# untitled.net
KiCad netlist of a schematic drawn in EAGLE
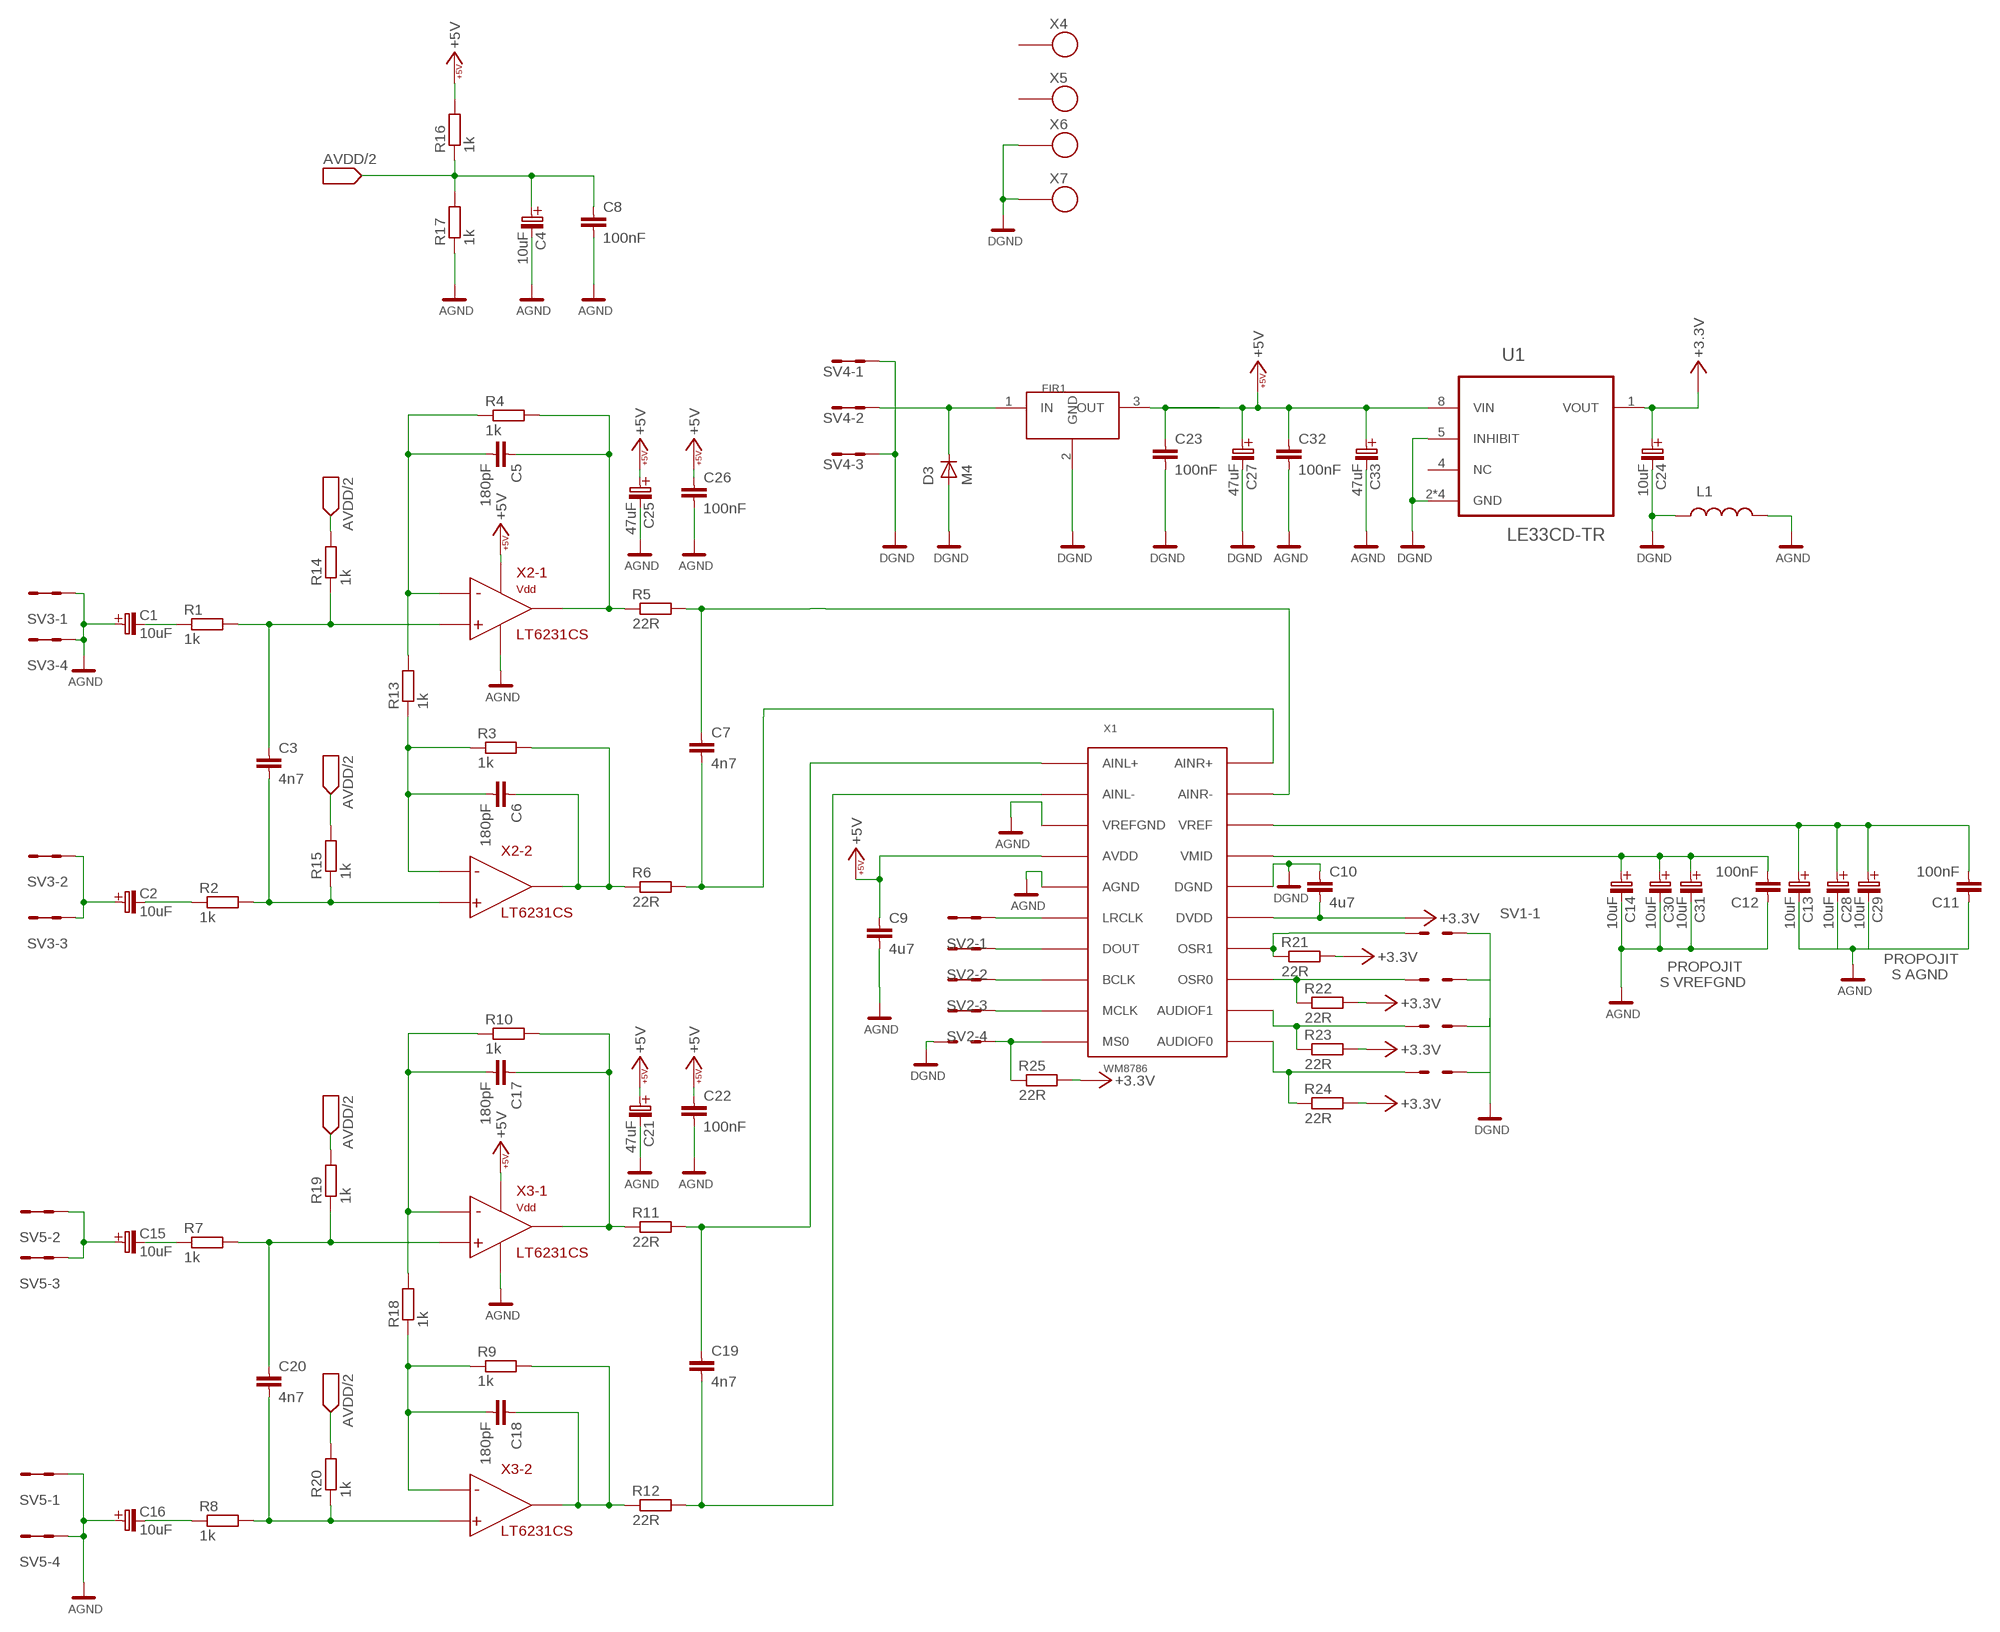
[diagram p0: schematic, sheet 1]

(export (version "E")
  (design (tool "Eeschema 10.0.6"))
  (components
    (comp (ref "C1") (value "10uF") (footprint "eagle-import:B") (libsource (lib "eagle-import") (part "B")))
    (comp (ref "C2") (value "10uF") (footprint "eagle-import:B") (libsource (lib "eagle-import") (part "B")))
    (comp (ref "C3")
      (value "4n7")
      (footprint "eagle-import:C0805")
      (libsource (lib "eagle-import") (part "C0805"))
    )
    (comp (ref "C4") (value "10uF") (footprint "eagle-import:B") (libsource (lib "eagle-import") (part "B")))
    (comp (ref "C5")
      (value "180pF")
      (footprint "eagle-import:C0805")
      (libsource (lib "eagle-import") (part "C0805"))
    )
    (comp (ref "C6")
      (value "180pF")
      (footprint "eagle-import:C0805")
      (libsource (lib "eagle-import") (part "C0805"))
    )
    (comp (ref "C7")
      (value "4n7")
      (footprint "eagle-import:C0805")
      (libsource (lib "eagle-import") (part "C0805"))
    )
    (comp (ref "C8")
      (value "100nF")
      (footprint "eagle-import:C0805")
      (libsource (lib "eagle-import") (part "C0805"))
    )
    (comp (ref "C9")
      (value "4u7")
      (footprint "eagle-import:C0805")
      (libsource (lib "eagle-import") (part "C0805"))
    )
    (comp (ref "C10")
      (value "4u7")
      (footprint "eagle-import:C0805")
      (libsource (lib "eagle-import") (part "C0805"))
    )
    (comp (ref "C11")
      (value "100nF")
      (footprint "eagle-import:C0805")
      (libsource (lib "eagle-import") (part "C0805"))
    )
    (comp (ref "C12")
      (value "100nF")
      (footprint "eagle-import:C0805")
      (libsource (lib "eagle-import") (part "C0805"))
    )
    (comp (ref "C13") (value "10uF") (footprint "eagle-import:B") (libsource (lib "eagle-import") (part "B")))
    (comp (ref "C14") (value "10uF") (footprint "eagle-import:B") (libsource (lib "eagle-import") (part "B")))
    (comp (ref "C15") (value "10uF") (footprint "eagle-import:B") (libsource (lib "eagle-import") (part "B")))
    (comp (ref "C16") (value "10uF") (footprint "eagle-import:B") (libsource (lib "eagle-import") (part "B")))
    (comp (ref "C17")
      (value "180pF")
      (footprint "eagle-import:C0805")
      (libsource (lib "eagle-import") (part "C0805"))
    )
    (comp (ref "C18")
      (value "180pF")
      (footprint "eagle-import:C0805")
      (libsource (lib "eagle-import") (part "C0805"))
    )
    (comp (ref "C19")
      (value "4n7")
      (footprint "eagle-import:C0805")
      (libsource (lib "eagle-import") (part "C0805"))
    )
    (comp (ref "C20")
      (value "4n7")
      (footprint "eagle-import:C0805")
      (libsource (lib "eagle-import") (part "C0805"))
    )
    (comp (ref "C21") (value "47uF") (footprint "eagle-import:B") (libsource (lib "eagle-import") (part "B")))
    (comp (ref "C22")
      (value "100nF")
      (footprint "eagle-import:C0805")
      (libsource (lib "eagle-import") (part "C0805"))
    )
    (comp (ref "C23")
      (value "100nF")
      (footprint "eagle-import:C0805")
      (libsource (lib "eagle-import") (part "C0805"))
    )
    (comp (ref "C24") (value "10uF") (footprint "eagle-import:B") (libsource (lib "eagle-import") (part "B")))
    (comp (ref "C25") (value "47uF") (footprint "eagle-import:B") (libsource (lib "eagle-import") (part "B")))
    (comp (ref "C26")
      (value "100nF")
      (footprint "eagle-import:C0805")
      (libsource (lib "eagle-import") (part "C0805"))
    )
    (comp (ref "C27") (value "47uF") (footprint "eagle-import:B") (libsource (lib "eagle-import") (part "B")))
    (comp (ref "C28") (value "10uF") (footprint "eagle-import:B") (libsource (lib "eagle-import") (part "B")))
    (comp (ref "C29") (value "10uF") (footprint "eagle-import:B") (libsource (lib "eagle-import") (part "B")))
    (comp (ref "C30") (value "10uF") (footprint "eagle-import:B") (libsource (lib "eagle-import") (part "B")))
    (comp (ref "C31") (value "10uF") (footprint "eagle-import:B") (libsource (lib "eagle-import") (part "B")))
    (comp (ref "C32")
      (value "100nF")
      (footprint "eagle-import:C0805")
      (libsource (lib "eagle-import") (part "C0805"))
    )
    (comp (ref "C33") (value "47uF") (footprint "eagle-import:B") (libsource (lib "eagle-import") (part "B")))
    (comp (ref "D3")
      (value "M4")
      (footprint "eagle-import:SMA")
      (libsource (lib "eagle-import") (part "D-OB.SMA"))
    )
    (comp (ref "FIR1")
      (value "FILTR0805")
      (footprint "eagle-import:F0805")
      (libsource (lib "eagle-import") (part "FILTR0805"))
    )
    (comp (ref "L1")
      (value "L0805")
      (footprint "eagle-import:L0805")
      (libsource (lib "eagle-import") (part "L0805"))
    )
    (comp (ref "R1")
      (value "1k")
      (footprint "eagle-import:0805")
      (libsource (lib "eagle-import") (part "R0805"))
    )
    (comp (ref "R2")
      (value "1k")
      (footprint "eagle-import:0805")
      (libsource (lib "eagle-import") (part "R0805"))
    )
    (comp (ref "R3")
      (value "1k")
      (footprint "eagle-import:0805")
      (libsource (lib "eagle-import") (part "R0805"))
    )
    (comp (ref "R4")
      (value "1k")
      (footprint "eagle-import:0805")
      (libsource (lib "eagle-import") (part "R0805"))
    )
    (comp (ref "R5")
      (value "22R")
      (footprint "eagle-import:0805")
      (libsource (lib "eagle-import") (part "R0805"))
    )
    (comp (ref "R6")
      (value "22R")
      (footprint "eagle-import:0805")
      (libsource (lib "eagle-import") (part "R0805"))
    )
    (comp (ref "R7")
      (value "1k")
      (footprint "eagle-import:0805")
      (libsource (lib "eagle-import") (part "R0805"))
    )
    (comp (ref "R8")
      (value "1k")
      (footprint "eagle-import:0805")
      (libsource (lib "eagle-import") (part "R0805"))
    )
    (comp (ref "R9")
      (value "1k")
      (footprint "eagle-import:0805")
      (libsource (lib "eagle-import") (part "R0805"))
    )
    (comp (ref "R10")
      (value "1k")
      (footprint "eagle-import:0805")
      (libsource (lib "eagle-import") (part "R0805"))
    )
    (comp (ref "R11")
      (value "22R")
      (footprint "eagle-import:0805")
      (libsource (lib "eagle-import") (part "R0805"))
    )
    (comp (ref "R12")
      (value "22R")
      (footprint "eagle-import:0805")
      (libsource (lib "eagle-import") (part "R0805"))
    )
    (comp (ref "R13")
      (value "1k")
      (footprint "eagle-import:0805")
      (libsource (lib "eagle-import") (part "R0805"))
    )
    (comp (ref "R14")
      (value "1k")
      (footprint "eagle-import:0805")
      (libsource (lib "eagle-import") (part "R0805"))
    )
    (comp (ref "R15")
      (value "1k")
      (footprint "eagle-import:0805")
      (libsource (lib "eagle-import") (part "R0805"))
    )
    (comp (ref "R16")
      (value "1k")
      (footprint "eagle-import:0805")
      (libsource (lib "eagle-import") (part "R0805"))
    )
    (comp (ref "R17")
      (value "1k")
      (footprint "eagle-import:0805")
      (libsource (lib "eagle-import") (part "R0805"))
    )
    (comp (ref "R18")
      (value "1k")
      (footprint "eagle-import:0805")
      (libsource (lib "eagle-import") (part "R0805"))
    )
    (comp (ref "R19")
      (value "1k")
      (footprint "eagle-import:0805")
      (libsource (lib "eagle-import") (part "R0805"))
    )
    (comp (ref "R20")
      (value "1k")
      (footprint "eagle-import:0805")
      (libsource (lib "eagle-import") (part "R0805"))
    )
    (comp (ref "R21")
      (value "22R")
      (footprint "eagle-import:0805")
      (libsource (lib "eagle-import") (part "R0805"))
    )
    (comp (ref "R22")
      (value "22R")
      (footprint "eagle-import:0805")
      (libsource (lib "eagle-import") (part "R0805"))
    )
    (comp (ref "R23")
      (value "22R")
      (footprint "eagle-import:0805")
      (libsource (lib "eagle-import") (part "R0805"))
    )
    (comp (ref "R24")
      (value "22R")
      (footprint "eagle-import:0805")
      (libsource (lib "eagle-import") (part "R0805"))
    )
    (comp (ref "R25")
      (value "22R")
      (footprint "eagle-import:0805")
      (libsource (lib "eagle-import") (part "R0805"))
    )
    (comp (ref "SV1")
      (value "MA05-3")
      (footprint "eagle-import:MA05-2")
      (libsource (lib "eagle-import") (part "MA05-3"))
    )
    (comp (ref "SV2")
      (value "MA04-2")
      (footprint "eagle-import:MA04-2")
      (libsource (lib "eagle-import") (part "MA04-2"))
    )
    (comp (ref "SV3")
      (value "MA04-2")
      (footprint "eagle-import:MA04-2")
      (libsource (lib "eagle-import") (part "MA04-2"))
    )
    (comp (ref "SV4")
      (value "MA03-2")
      (footprint "eagle-import:MA03-2")
      (libsource (lib "eagle-import") (part "MA03-2"))
    )
    (comp (ref "SV5")
      (value "MA04-2")
      (footprint "eagle-import:MA04-2")
      (libsource (lib "eagle-import") (part "MA04-2"))
    )
    (comp (ref "U1")
      (value "LE33CD-TR")
      (footprint "eagle-import:SOIC127P600X175-8N")
      (libsource (lib "eagle-import") (part "LE33CD-TR"))
    )
    (comp (ref "X1")
      (value "WM8786")
      (footprint "eagle-import:SSOP20")
      (libsource (lib "eagle-import") (part "WM8786"))
    )
    (comp (ref "X2")
      (value "LT6231CS")
      (footprint "eagle-import:SO8")
      (libsource (lib "eagle-import") (part "LT6231CS"))
    )
    (comp (ref "X3")
      (value "LT6231CS")
      (footprint "eagle-import:SO8")
      (libsource (lib "eagle-import") (part "LT6231CS"))
    )
    (comp (ref "X4")
      (value "SROUB3M")
      (footprint "eagle-import:SROUB3M")
      (libsource (lib "eagle-import") (part "SROUB3M"))
    )
    (comp (ref "X5")
      (value "SROUB3M")
      (footprint "eagle-import:SROUB3M")
      (libsource (lib "eagle-import") (part "SROUB3M"))
    )
    (comp (ref "X6")
      (value "SROUB3M")
      (footprint "eagle-import:SROUB3M")
      (libsource (lib "eagle-import") (part "SROUB3M"))
    )
    (comp (ref "X7")
      (value "SROUB3M")
      (footprint "eagle-import:SROUB3M")
      (libsource (lib "eagle-import") (part "SROUB3M"))
    )
  )
  (nets
    (net (code "1") (name "+3.3V") (class "Default")
      (node (ref "C10") (pin "2") (pinfunction "2_2") (pintype "passive"))
      (node (ref "C24") (pin "+") (pinfunction "C_EL+_+") (pintype "passive"))
      (node (ref "R21") (pin "2") (pinfunction "2_2") (pintype "passive"))
      (node (ref "R22") (pin "2") (pinfunction "2_2") (pintype "passive"))
      (node (ref "R23") (pin "2") (pinfunction "2_2") (pintype "passive"))
      (node (ref "R24") (pin "2") (pinfunction "2_2") (pintype "passive"))
      (node (ref "R25") (pin "2") (pinfunction "2_2") (pintype "passive"))
      (node (ref "U1") (pin "1") (pinfunction "VOUT_1") (pintype "output"))
      (node (ref "X1") (pin "15") (pinfunction "DVDD_15") (pintype "bidirectional"))
    )
    (net (code "2") (name "+5V") (class "Default")
      (node (ref "C21") (pin "+") (pinfunction "C_EL+_+") (pintype "passive"))
      (node (ref "C22") (pin "1") (pinfunction "1_1") (pintype "passive"))
      (node (ref "C23") (pin "1") (pinfunction "1_1") (pintype "passive"))
      (node (ref "C25") (pin "+") (pinfunction "C_EL+_+") (pintype "passive"))
      (node (ref "C26") (pin "1") (pinfunction "1_1") (pintype "passive"))
      (node (ref "C27") (pin "+") (pinfunction "C_EL+_+") (pintype "passive"))
      (node (ref "C32") (pin "1") (pinfunction "1_1") (pintype "passive"))
      (node (ref "C33") (pin "+") (pinfunction "C_EL+_+") (pintype "passive"))
      (node (ref "C9") (pin "1") (pinfunction "1_1") (pintype "passive"))
      (node (ref "FIR1") (pin "3") (pinfunction "OUT_3") (pintype "bidirectional"))
      (node (ref "R16") (pin "2") (pinfunction "2_2") (pintype "passive"))
      (node (ref "U1") (pin "8") (pinfunction "VIN_8") (pintype "power_in"))
      (node (ref "X1") (pin "4") (pinfunction "AVDD_4") (pintype "bidirectional"))
      (node (ref "X2") (pin "8") (pinfunction "VDD_8") (pintype "bidirectional"))
      (node (ref "X3") (pin "8") (pinfunction "VDD_8") (pintype "bidirectional"))
    )
    (net (code "3") (name "/AVDD{slash}2") (class "Default")
      (node (ref "C4") (pin "+") (pinfunction "C_EL+_+") (pintype "passive"))
      (node (ref "C8") (pin "1") (pinfunction "1_1") (pintype "passive"))
      (node (ref "R14") (pin "2") (pinfunction "2_2") (pintype "passive"))
      (node (ref "R15") (pin "2") (pinfunction "2_2") (pintype "passive"))
      (node (ref "R16") (pin "1") (pinfunction "1_1") (pintype "passive"))
      (node (ref "R17") (pin "2") (pinfunction "2_2") (pintype "passive"))
      (node (ref "R19") (pin "2") (pinfunction "2_2") (pintype "passive"))
      (node (ref "R20") (pin "2") (pinfunction "2_2") (pintype "passive"))
    )
    (net (code "4") (name "AGND") (class "Default")
      (node (ref "C1") (pin "+") (pinfunction "C_EL+_+") (pintype "passive"))
      (node (ref "C11") (pin "1") (pinfunction "1_1") (pintype "passive"))
      (node (ref "C12") (pin "1") (pinfunction "1_1") (pintype "passive"))
      (node (ref "C13") (pin "-") (pinfunction "C_EL-_-") (pintype "passive"))
      (node (ref "C14") (pin "-") (pinfunction "C_EL-_-") (pintype "passive"))
      (node (ref "C16") (pin "+") (pinfunction "C_EL+_+") (pintype "passive"))
      (node (ref "C21") (pin "-") (pinfunction "C_EL-_-") (pintype "passive"))
      (node (ref "C22") (pin "2") (pinfunction "2_2") (pintype "passive"))
      (node (ref "C25") (pin "-") (pinfunction "C_EL-_-") (pintype "passive"))
      (node (ref "C26") (pin "2") (pinfunction "2_2") (pintype "passive"))
      (node (ref "C28") (pin "-") (pinfunction "C_EL-_-") (pintype "passive"))
      (node (ref "C29") (pin "-") (pinfunction "C_EL-_-") (pintype "passive"))
      (node (ref "C30") (pin "-") (pinfunction "C_EL-_-") (pintype "passive"))
      (node (ref "C31") (pin "-") (pinfunction "C_EL-_-") (pintype "passive"))
      (node (ref "C32") (pin "2") (pinfunction "2_2") (pintype "passive"))
      (node (ref "C33") (pin "-") (pinfunction "C_EL-_-") (pintype "passive"))
      (node (ref "C4") (pin "-") (pinfunction "C_EL-_-") (pintype "passive"))
      (node (ref "C8") (pin "2") (pinfunction "2_2") (pintype "passive"))
      (node (ref "C9") (pin "2") (pinfunction "2_2") (pintype "passive"))
      (node (ref "L1") (pin "2") (pinfunction "2_2") (pintype "passive"))
      (node (ref "R17") (pin "1") (pinfunction "1_1") (pintype "passive"))
      (node (ref "SV3") (pin "1") (pinfunction "K_1") (pintype "passive"))
      (node (ref "SV3") (pin "2") (pinfunction "K_2") (pintype "passive"))
      (node (ref "SV3") (pin "7") (pinfunction "K_7") (pintype "passive"))
      (node (ref "SV3") (pin "8") (pinfunction "K_8") (pintype "passive"))
      (node (ref "SV5") (pin "1") (pinfunction "K_1") (pintype "passive"))
      (node (ref "SV5") (pin "2") (pinfunction "K_2") (pintype "passive"))
      (node (ref "SV5") (pin "7") (pinfunction "K_7") (pintype "passive"))
      (node (ref "SV5") (pin "8") (pinfunction "K_8") (pintype "passive"))
      (node (ref "X1") (pin "3") (pinfunction "VREFGND_3") (pintype "bidirectional"))
      (node (ref "X1") (pin "5") (pinfunction "AGND_5") (pintype "bidirectional"))
      (node (ref "X2") (pin "4") (pinfunction "GND_4") (pintype "bidirectional"))
      (node (ref "X3") (pin "4") (pinfunction "GND_4") (pintype "bidirectional"))
    )
    (net (code "5") (name "DGND") (class "Default")
      (node (ref "C10") (pin "1") (pinfunction "1_1") (pintype "passive"))
      (node (ref "C23") (pin "2") (pinfunction "2_2") (pintype "passive"))
      (node (ref "C24") (pin "-") (pinfunction "C_EL-_-") (pintype "passive"))
      (node (ref "C27") (pin "-") (pinfunction "C_EL-_-") (pintype "passive"))
      (node (ref "D3") (pin "A") (pinfunction "A_A") (pintype "passive"))
      (node (ref "FIR1") (pin "2") (pinfunction "GND_2") (pintype "passive"))
      (node (ref "L1") (pin "1") (pinfunction "1_1") (pintype "passive"))
      (node (ref "SV1") (pin "1") (pinfunction "P$1_1") (pintype "passive"))
      (node (ref "SV1") (pin "3") (pinfunction "P$1_3") (pintype "passive"))
      (node (ref "SV1") (pin "5") (pinfunction "P$1_5") (pintype "passive"))
      (node (ref "SV1") (pin "7") (pinfunction "P$1_7") (pintype "passive"))
      (node (ref "SV1") (pin "9") (pinfunction "P$1_9") (pintype "passive"))
      (node (ref "SV4") (pin "1") (pinfunction "K_1") (pintype "passive"))
      (node (ref "SV4") (pin "2") (pinfunction "K_2") (pintype "passive"))
      (node (ref "SV4") (pin "5") (pinfunction "K_5") (pintype "passive"))
      (node (ref "SV4") (pin "6") (pinfunction "K_6") (pintype "passive"))
      (node (ref "U1") (pin "2") (pinfunction "GND_2") (pintype "passive"))
      (node (ref "U1") (pin "3") (pinfunction "GND_3") (pintype "passive"))
      (node (ref "U1") (pin "5") (pinfunction "INHIBIT_5") (pintype "passive"))
      (node (ref "U1") (pin "6") (pinfunction "GND_6") (pintype "passive"))
      (node (ref "U1") (pin "7") (pinfunction "GND_7") (pintype "passive"))
      (node (ref "X1") (pin "16") (pinfunction "DGND_16") (pintype "bidirectional"))
      (node (ref "X6") (pin "P$1") (pinfunction "P$1_P$1") (pintype "bidirectional"))
      (node (ref "X7") (pin "P$1") (pinfunction "P$1_P$1") (pintype "bidirectional"))
    )
    (net (code "6") (name "Net-(C1-C_EL-)") (class "Default")
      (node (ref "C1") (pin "-") (pinfunction "C_EL-_-") (pintype "passive"))
      (node (ref "R1") (pin "1") (pinfunction "1_1") (pintype "passive"))
    )
    (net (code "7") (name "Net-(C2-C_EL+)") (class "Default")
      (node (ref "C2") (pin "+") (pinfunction "C_EL+_+") (pintype "passive"))
      (node (ref "SV3") (pin "3") (pinfunction "K_3") (pintype "passive"))
      (node (ref "SV3") (pin "4") (pinfunction "K_4") (pintype "passive"))
      (node (ref "SV3") (pin "5") (pinfunction "K_5") (pintype "passive"))
      (node (ref "SV3") (pin "6") (pinfunction "K_6") (pintype "passive"))
    )
    (net (code "8") (name "Net-(C2-C_EL-)") (class "Default")
      (node (ref "C2") (pin "-") (pinfunction "C_EL-_-") (pintype "passive"))
      (node (ref "R2") (pin "1") (pinfunction "1_1") (pintype "passive"))
    )
    (net (code "9") (name "Net-(C13-C_EL+)") (class "Default")
      (node (ref "C11") (pin "2") (pinfunction "2_2") (pintype "passive"))
      (node (ref "C13") (pin "+") (pinfunction "C_EL+_+") (pintype "passive"))
      (node (ref "C28") (pin "+") (pinfunction "C_EL+_+") (pintype "passive"))
      (node (ref "C29") (pin "+") (pinfunction "C_EL+_+") (pintype "passive"))
      (node (ref "X1") (pin "18") (pinfunction "VREF_18") (pintype "bidirectional"))
    )
    (net (code "10") (name "Net-(C14-C_EL+)") (class "Default")
      (node (ref "C12") (pin "2") (pinfunction "2_2") (pintype "passive"))
      (node (ref "C14") (pin "+") (pinfunction "C_EL+_+") (pintype "passive"))
      (node (ref "C30") (pin "+") (pinfunction "C_EL+_+") (pintype "passive"))
      (node (ref "C31") (pin "+") (pinfunction "C_EL+_+") (pintype "passive"))
      (node (ref "X1") (pin "17") (pinfunction "VMID_17") (pintype "bidirectional"))
    )
    (net (code "11") (name "Net-(C15-C_EL+)") (class "Default")
      (node (ref "C15") (pin "+") (pinfunction "C_EL+_+") (pintype "passive"))
      (node (ref "SV5") (pin "3") (pinfunction "K_3") (pintype "passive"))
      (node (ref "SV5") (pin "4") (pinfunction "K_4") (pintype "passive"))
      (node (ref "SV5") (pin "5") (pinfunction "K_5") (pintype "passive"))
      (node (ref "SV5") (pin "6") (pinfunction "K_6") (pintype "passive"))
    )
    (net (code "12") (name "Net-(C15-C_EL-)") (class "Default")
      (node (ref "C15") (pin "-") (pinfunction "C_EL-_-") (pintype "passive"))
      (node (ref "R7") (pin "1") (pinfunction "1_1") (pintype "passive"))
    )
    (net (code "13") (name "Net-(C16-C_EL-)") (class "Default")
      (node (ref "C16") (pin "-") (pinfunction "C_EL-_-") (pintype "passive"))
      (node (ref "R8") (pin "1") (pinfunction "1_1") (pintype "passive"))
    )
    (net (code "14") (name "Net-(D3-C)") (class "Default")
      (node (ref "D3") (pin "K") (pinfunction "C_K") (pintype "passive"))
      (node (ref "FIR1") (pin "1") (pinfunction "IN_1") (pintype "bidirectional"))
      (node (ref "SV4") (pin "3") (pinfunction "K_3") (pintype "passive"))
      (node (ref "SV4") (pin "4") (pinfunction "K_4") (pintype "passive"))
    )
    (net (code "15") (name "Net-(SV1B-P$1)") (class "Default")
      (node (ref "R25") (pin "1") (pinfunction "1_1") (pintype "passive"))
      (node (ref "SV1") (pin "10") (pinfunction "P$1_10") (pintype "passive"))
      (node (ref "X1") (pin "10") (pinfunction "MS0_10") (pintype "bidirectional"))
    )
    (net (code "16") (name "Net-(SV1C-P$1)") (class "Default")
      (node (ref "R21") (pin "1") (pinfunction "1_1") (pintype "passive"))
      (node (ref "SV1") (pin "2") (pinfunction "P$1_2") (pintype "passive"))
      (node (ref "X1") (pin "14") (pinfunction "OSR1_14") (pintype "bidirectional"))
    )
    (net (code "17") (name "Net-(SV1E-P$1)") (class "Default")
      (node (ref "R22") (pin "1") (pinfunction "1_1") (pintype "passive"))
      (node (ref "SV1") (pin "4") (pinfunction "P$1_4") (pintype "passive"))
      (node (ref "X1") (pin "13") (pinfunction "OSR0_13") (pintype "bidirectional"))
    )
    (net (code "18") (name "Net-(SV1G-P$1)") (class "Default")
      (node (ref "R23") (pin "1") (pinfunction "1_1") (pintype "passive"))
      (node (ref "SV1") (pin "6") (pinfunction "P$1_6") (pintype "passive"))
      (node (ref "X1") (pin "12") (pinfunction "AUDIOF1_12") (pintype "bidirectional"))
    )
    (net (code "19") (name "Net-(SV1I-P$1)") (class "Default")
      (node (ref "R24") (pin "1") (pinfunction "1_1") (pintype "passive"))
      (node (ref "SV1") (pin "8") (pinfunction "P$1_8") (pintype "passive"))
      (node (ref "X1") (pin "11") (pinfunction "AUDIOF0_11") (pintype "bidirectional"))
    )
    (net (code "20") (name "Net-(X1-AINL+)") (class "Default")
      (node (ref "C19") (pin "1") (pinfunction "1_1") (pintype "passive"))
      (node (ref "R11") (pin "2") (pinfunction "2_2") (pintype "passive"))
      (node (ref "X1") (pin "1") (pinfunction "AINL+_1") (pintype "bidirectional"))
    )
    (net (code "21") (name "Net-(X1-AINL-)") (class "Default")
      (node (ref "C19") (pin "2") (pinfunction "2_2") (pintype "passive"))
      (node (ref "R12") (pin "2") (pinfunction "2_2") (pintype "passive"))
      (node (ref "X1") (pin "2") (pinfunction "AINL-_2") (pintype "bidirectional"))
    )
    (net (code "22") (name "Net-(X1-AINR+)") (class "Default")
      (node (ref "C7") (pin "2") (pinfunction "2_2") (pintype "passive"))
      (node (ref "R6") (pin "2") (pinfunction "2_2") (pintype "passive"))
      (node (ref "X1") (pin "20") (pinfunction "AINR+_20") (pintype "bidirectional"))
    )
    (net (code "23") (name "Net-(X1-AINR-)") (class "Default")
      (node (ref "C7") (pin "1") (pinfunction "1_1") (pintype "passive"))
      (node (ref "R5") (pin "2") (pinfunction "2_2") (pintype "passive"))
      (node (ref "X1") (pin "19") (pinfunction "AINR-_19") (pintype "bidirectional"))
    )
    (net (code "24") (name "Net-(X1-BCLK)") (class "Default")
      (node (ref "SV2") (pin "5") (pinfunction "K_5") (pintype "passive"))
      (node (ref "SV2") (pin "6") (pinfunction "K_6") (pintype "passive"))
      (node (ref "X1") (pin "8") (pinfunction "BCLK_8") (pintype "bidirectional"))
    )
    (net (code "25") (name "Net-(X1-DOUT)") (class "Default")
      (node (ref "SV2") (pin "3") (pinfunction "K_3") (pintype "passive"))
      (node (ref "SV2") (pin "4") (pinfunction "K_4") (pintype "passive"))
      (node (ref "X1") (pin "7") (pinfunction "DOUT_7") (pintype "bidirectional"))
    )
    (net (code "26") (name "Net-(X1-LRCLK)") (class "Default")
      (node (ref "SV2") (pin "1") (pinfunction "K_1") (pintype "passive"))
      (node (ref "SV2") (pin "2") (pinfunction "K_2") (pintype "passive"))
      (node (ref "X1") (pin "6") (pinfunction "LRCLK_6") (pintype "bidirectional"))
    )
    (net (code "27") (name "Net-(X1-MCLK)") (class "Default")
      (node (ref "SV2") (pin "7") (pinfunction "K_7") (pintype "passive"))
      (node (ref "SV2") (pin "8") (pinfunction "K_8") (pintype "passive"))
      (node (ref "X1") (pin "9") (pinfunction "MCLK_9") (pintype "bidirectional"))
    )
    (net (code "28") (name "Net-(X2A-+)") (class "Default")
      (node (ref "C3") (pin "1") (pinfunction "1_1") (pintype "passive"))
      (node (ref "R1") (pin "2") (pinfunction "2_2") (pintype "passive"))
      (node (ref "R14") (pin "1") (pinfunction "1_1") (pintype "passive"))
      (node (ref "X2") (pin "3") (pinfunction "+_3") (pintype "bidirectional"))
    )
    (net (code "29") (name "Net-(X2A--)") (class "Default")
      (node (ref "C5") (pin "2") (pinfunction "2_2") (pintype "passive"))
      (node (ref "R13") (pin "2") (pinfunction "2_2") (pintype "passive"))
      (node (ref "R4") (pin "1") (pinfunction "1_1") (pintype "passive"))
      (node (ref "X2") (pin "2") (pinfunction "-_2") (pintype "bidirectional"))
    )
    (net (code "30") (name "Net-(X2A-VOUT)") (class "Default")
      (node (ref "C5") (pin "1") (pinfunction "1_1") (pintype "passive"))
      (node (ref "R4") (pin "2") (pinfunction "2_2") (pintype "passive"))
      (node (ref "R5") (pin "1") (pinfunction "1_1") (pintype "passive"))
      (node (ref "X2") (pin "1") (pinfunction "VOUT_1") (pintype "bidirectional"))
    )
    (net (code "31") (name "Net-(X2B-+)") (class "Default")
      (node (ref "C3") (pin "2") (pinfunction "2_2") (pintype "passive"))
      (node (ref "R15") (pin "1") (pinfunction "1_1") (pintype "passive"))
      (node (ref "R2") (pin "2") (pinfunction "2_2") (pintype "passive"))
      (node (ref "X2") (pin "5") (pinfunction "+_5") (pintype "bidirectional"))
    )
    (net (code "32") (name "Net-(X2B--)") (class "Default")
      (node (ref "C6") (pin "2") (pinfunction "2_2") (pintype "passive"))
      (node (ref "R13") (pin "1") (pinfunction "1_1") (pintype "passive"))
      (node (ref "R3") (pin "1") (pinfunction "1_1") (pintype "passive"))
      (node (ref "X2") (pin "6") (pinfunction "-_6") (pintype "bidirectional"))
    )
    (net (code "33") (name "Net-(X2B-VOUT)") (class "Default")
      (node (ref "C6") (pin "1") (pinfunction "1_1") (pintype "passive"))
      (node (ref "R3") (pin "2") (pinfunction "2_2") (pintype "passive"))
      (node (ref "R6") (pin "1") (pinfunction "1_1") (pintype "passive"))
      (node (ref "X2") (pin "7") (pinfunction "VOUT_7") (pintype "bidirectional"))
    )
    (net (code "34") (name "Net-(X3A-+)") (class "Default")
      (node (ref "C20") (pin "1") (pinfunction "1_1") (pintype "passive"))
      (node (ref "R19") (pin "1") (pinfunction "1_1") (pintype "passive"))
      (node (ref "R7") (pin "2") (pinfunction "2_2") (pintype "passive"))
      (node (ref "X3") (pin "3") (pinfunction "+_3") (pintype "bidirectional"))
    )
    (net (code "35") (name "Net-(X3A--)") (class "Default")
      (node (ref "C17") (pin "2") (pinfunction "2_2") (pintype "passive"))
      (node (ref "R10") (pin "1") (pinfunction "1_1") (pintype "passive"))
      (node (ref "R18") (pin "2") (pinfunction "2_2") (pintype "passive"))
      (node (ref "X3") (pin "2") (pinfunction "-_2") (pintype "bidirectional"))
    )
    (net (code "36") (name "Net-(X3A-VOUT)") (class "Default")
      (node (ref "C17") (pin "1") (pinfunction "1_1") (pintype "passive"))
      (node (ref "R10") (pin "2") (pinfunction "2_2") (pintype "passive"))
      (node (ref "R11") (pin "1") (pinfunction "1_1") (pintype "passive"))
      (node (ref "X3") (pin "1") (pinfunction "VOUT_1") (pintype "bidirectional"))
    )
    (net (code "37") (name "Net-(X3B-+)") (class "Default")
      (node (ref "C20") (pin "2") (pinfunction "2_2") (pintype "passive"))
      (node (ref "R20") (pin "1") (pinfunction "1_1") (pintype "passive"))
      (node (ref "R8") (pin "2") (pinfunction "2_2") (pintype "passive"))
      (node (ref "X3") (pin "5") (pinfunction "+_5") (pintype "bidirectional"))
    )
    (net (code "38") (name "Net-(X3B--)") (class "Default")
      (node (ref "C18") (pin "2") (pinfunction "2_2") (pintype "passive"))
      (node (ref "R18") (pin "1") (pinfunction "1_1") (pintype "passive"))
      (node (ref "R9") (pin "1") (pinfunction "1_1") (pintype "passive"))
      (node (ref "X3") (pin "6") (pinfunction "-_6") (pintype "bidirectional"))
    )
    (net (code "39") (name "Net-(X3B-VOUT)") (class "Default")
      (node (ref "C18") (pin "1") (pinfunction "1_1") (pintype "passive"))
      (node (ref "R12") (pin "1") (pinfunction "1_1") (pintype "passive"))
      (node (ref "R9") (pin "2") (pinfunction "2_2") (pintype "passive"))
      (node (ref "X3") (pin "7") (pinfunction "VOUT_7") (pintype "bidirectional"))
    )
    (net (code "40") (name "unconnected-(U1-NC-Pad4)") (class "Default")
      (node (ref "U1") (pin "4") (pinfunction "NC_4") (pintype "no_connect"))
    )
    (net (code "41") (name "unconnected-(X4-PadP$1)") (class "Default")
      (node (ref "X4") (pin "P$1") (pinfunction "P$1_P$1") (pintype "bidirectional"))
    )
    (net (code "42") (name "unconnected-(X5-PadP$1)") (class "Default")
      (node (ref "X5") (pin "P$1") (pinfunction "P$1_P$1") (pintype "bidirectional"))
    )
  )
)
